# Blue_Pill_v1_0.net
KiCad netlist of a schematic drawn in Altium Designer
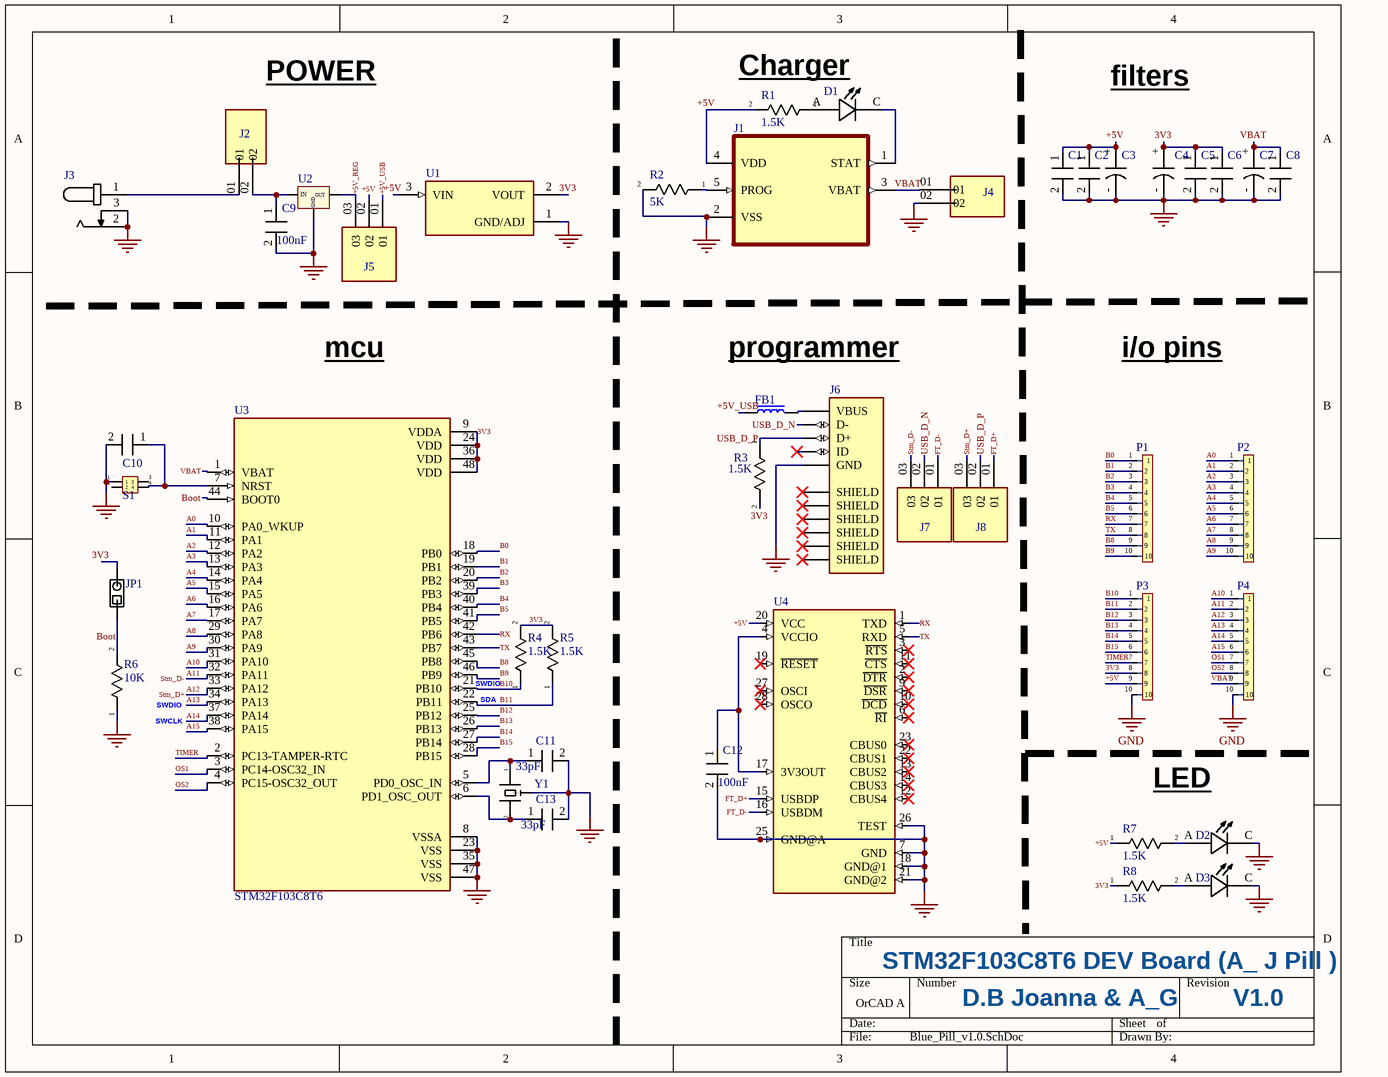
[diagram p0: Blue_Pill_v1.0.SchDoc]

(export (version "E")
  (design (tool "Eeschema 10.0.6"))
  (components
    (comp (ref "C1")
      (value "10nF")
      (footprint "CL21B104KACNNNC")
      (description "0.1 µF ±10% 25V Ceramic Capacitor X7R 0805 (2012 Metric)")
      (libsource (lib "Joanna_Integrated_Library") (part "CL21B104KACNNNC"))
    )
    (comp (ref "C2")
      (value "100nF")
      (footprint "CL21B104KACNNNC")
      (description "0.1 µF ±10% 25V Ceramic Capacitor X7R 0805 (2012 Metric)")
      (libsource (lib "Joanna_Integrated_Library") (part "CL21B104KACNNNC"))
    )
    (comp (ref "C3")
      (value "2.2UF")
      (footprint "10SVP4R7M")
      (description "4.7 µF 10 V Aluminum - Polymer Capacitors Radial, Can - SMD 240mOhm 2000 Hrs @ 105°C")
      (libsource (lib "Joanna_Integrated_Library") (part "10SVP4R7M"))
    )
    (comp (ref "C4")
      (value "2.2UF")
      (footprint "10SVP4R7M")
      (description "4.7 µF 10 V Aluminum - Polymer Capacitors Radial, Can - SMD 240mOhm 2000 Hrs @ 105°C")
      (libsource (lib "Joanna_Integrated_Library") (part "10SVP4R7M"))
    )
    (comp (ref "C5")
      (value "100nF")
      (footprint "CL21B104KACNNNC")
      (description "0.1 µF ±10% 25V Ceramic Capacitor X7R 0805 (2012 Metric)")
      (libsource (lib "Joanna_Integrated_Library") (part "CL21B104KACNNNC"))
    )
    (comp (ref "C6")
      (value "10nF")
      (footprint "CL21B104KACNNNC")
      (description "0.1 µF ±10% 25V Ceramic Capacitor X7R 0805 (2012 Metric)")
      (libsource (lib "Joanna_Integrated_Library") (part "CL21B104KACNNNC"))
    )
    (comp (ref "C7")
      (value "2.2UF")
      (footprint "10SVP4R7M")
      (description "4.7 µF 10 V Aluminum - Polymer Capacitors Radial, Can - SMD 240mOhm 2000 Hrs @ 105°C")
      (libsource (lib "Joanna_Integrated_Library") (part "10SVP4R7M"))
    )
    (comp (ref "C8")
      (value "100nF")
      (footprint "CL21B104KACNNNC")
      (description "0.1 µF ±10% 25V Ceramic Capacitor X7R 0805 (2012 Metric)")
      (libsource (lib "Joanna_Integrated_Library") (part "CL21B104KACNNNC"))
    )
    (comp (ref "C9")
      (value "100nF")
      (footprint "CL21B104KACNNNC")
      (description "0.1 µF ±10% 25V Ceramic Capacitor X7R 0805 (2012 Metric)")
      (libsource (lib "Joanna_Integrated_Library") (part "CL21B104KACNNNC"))
    )
    (comp (ref "C10")
      (value "100nF")
      (footprint "CL21B104KACNNNC")
      (description "0.1 µF ±10% 25V Ceramic Capacitor X7R 0805 (2012 Metric)")
      (libsource (lib "Joanna_Integrated_Library") (part "CL21B104KACNNNC"))
    )
    (comp (ref "C11")
      (value "33pF")
      (footprint "CC0805JKX7R7BB105")
      (description "1 µF ±5% 16V Ceramic Capacitor X7R 0805 (2012 Metric)")
      (libsource (lib "Joanna_Integrated_Library") (part "CC0805JKX7R7BB105"))
    )
    (comp (ref "C12")
      (value "100nF")
      (footprint "CL21B104KACNNNC")
      (description "0.1 µF ±10% 25V Ceramic Capacitor X7R 0805 (2012 Metric)")
      (libsource (lib "Joanna_Integrated_Library") (part "CL21B104KACNNNC"))
    )
    (comp (ref "C13")
      (value "33pF")
      (footprint "CC0805JKX7R7BB105")
      (description "1 µF ±5% 16V Ceramic Capacitor X7R 0805 (2012 Metric)")
      (libsource (lib "Joanna_Integrated_Library") (part "CC0805JKX7R7BB105"))
    )
    (comp (ref "D1")
      (value "LEDC2012X70N")
      (footprint "LEDC2012X70N")
      (description "SMD LED 0805")
      (libsource (lib "Joanna_Integrated_Library") (part "LEDC2012X70N"))
    )
    (comp (ref "D2")
      (value "LEDC2012X70N")
      (footprint "LEDC2012X70N")
      (description "SMD LED 0805")
      (libsource (lib "") (part "LEDC2012X70N_1"))
    )
    (comp (ref "D3")
      (value "LEDC2012X70N")
      (footprint "LEDC2012X70N")
      (description "SMD LED 0805")
      (libsource (lib "") (part "LEDC2012X70N_1"))
    )
    (comp (ref "FB1")
      (value "FB0805")
      (footprint "FB_0805")
      (description "Ferrite Bead SMD 0805")
      (libsource (lib "ph_lib") (part "FB_0805"))
    )
    (comp (ref "J1")
      (value "MCP73831T-2ACI/OT")
      (footprint "MCP73831_SOT95P280X145-5N")
      (description "Charger IC Lithium Ion/Polymer SOT-23-5")
      (fields (field (name "MF") "Microchip"))
      (libsource (lib "Joanna_Integrated_Library") (part "MCP73831T-2ACI/OT"))
    )
    (comp (ref "J2")
      (value "PINHEADER_2_61300211121")
      (footprint "PINHEADER_2_WURTH_61300211121")
      (description "Connector Header Through Hole 2 position 0.100 (2.54mm)")
      (fields (field (name "MF") "Wurth Elektronik") (field (name "MP") "61300211121"))
      (libsource (lib "") (part "PINHEADER_2_61300211121_1"))
    )
    (comp (ref "J3")
      (value "PJ-002AH")
      (footprint "PJ-002AH")
      (description "2.0 x 6.5 mm, 5.0 A, Horizontal, Through Hole, Dc Power Jack Connector")
      (libsource (lib "Joanna_Integrated_Library") (part "PJ-002AH"))
    )
    (comp (ref "J4")
      (value "PINHEADER_2_61300211121")
      (footprint "PINHEADER_2_WURTH_61300211121")
      (description "Connector Header Through Hole 2 position 0.100 (2.54mm)")
      (fields (field (name "MF") "Wurth Elektronik") (field (name "MP") "61300211121"))
      (libsource (lib "Joanna_Integrated_Library") (part "PINHEADER_2_61300211121"))
    )
    (comp (ref "J5")
      (value "PinHead_M_TSW-103-07-G-S")
      (footprint "PinHeader_M_SAMTEC_TSW-103-07-G-S")
      (fields (field (name "MP") "altium_native_batch"))
      (libsource (lib "Joanna_Integrated_Library") (part "PinHead_M_TSW-103-07-G-S"))
    )
    (comp (ref "J6")
      (value "USB_MICRO_USB3076-XX-X_REVC5")
      (footprint "USB_MICRO_GCT_USB3076-XX-X_REVC5")
      (fields (field (name "MP") "USB3076-30-A") (field (name "MF") "Global Connector Technology"))
      (libsource (lib "Joanna_Integrated_Library") (part "USB_MICRO_USB3076-XX-X_REVC5"))
    )
    (comp (ref "J7")
      (value "PinHead_M_TSW-103-07-G-S")
      (footprint "PinHeader_M_SAMTEC_TSW-103-07-G-S")
      (fields (field (name "MP") "altium_native_batch"))
      (libsource (lib "Joanna_Integrated_Library") (part "PinHead_M_TSW-103-07-G-S"))
    )
    (comp (ref "J8")
      (value "PinHead_M_TSW-103-07-G-S")
      (footprint "PinHeader_M_SAMTEC_TSW-103-07-G-S")
      (fields (field (name "MP") "altium_native_batch"))
      (libsource (lib "Joanna_Integrated_Library") (part "PinHead_M_TSW-103-07-G-S"))
    )
    (comp (ref "JP1")
      (value "Solder Jumper")
      (footprint "SolderJumper_Single")
      (description "Solder Jumper Single 0.5mm Pitch")
      (libsource (lib "ph_lib") (part "SolderJumper_Single"))
    )
    (comp (ref "P1")
      (value "NPPN101BFCN-RC")
      (footprint "NPPN101BFCN-RC")
      (description "10 Position Header Connector 0.079\" (2.00mm) Through Hole Gold")
      (libsource (lib "Joanna_Integrated_Library") (part "NPPN101BFCN-RC"))
    )
    (comp (ref "P2")
      (value "NPPN101BFCN-RC")
      (footprint "NPPN101BFCN-RC")
      (description "10 Position Header Connector 0.079\" (2.00mm) Through Hole Gold")
      (libsource (lib "Joanna_Integrated_Library") (part "NPPN101BFCN-RC"))
    )
    (comp (ref "P3")
      (value "NPPN101BFCN-RC")
      (footprint "NPPN101BFCN-RC")
      (description "10 Position Header Connector 0.079\" (2.00mm) Through Hole Gold")
      (libsource (lib "Joanna_Integrated_Library") (part "NPPN101BFCN-RC"))
    )
    (comp (ref "P4")
      (value "NPPN101BFCN-RC")
      (footprint "NPPN101BFCN-RC")
      (description "10 Position Header Connector 0.079\" (2.00mm) Through Hole Gold")
      (libsource (lib "Joanna_Integrated_Library") (part "NPPN101BFCN-RC"))
    )
    (comp (ref "R1")
      (value "1.5K")
      (footprint "RMCF0805FT8K06")
      (description "8.06 kOhms ±1% 0.125W, 1/8W Chip Resistor 0805 (2012 Metric) Automotive AEC-Q200 Thick Film")
      (libsource (lib "Joanna_Integrated_Library") (part "RMCF0805FT8K06"))
    )
    (comp (ref "R2")
      (value "5K")
      (footprint "RMCF0805FT8K06")
      (description "8.06 kOhms ±1% 0.125W, 1/8W Chip Resistor 0805 (2012 Metric) Automotive AEC-Q200 Thick Film")
      (libsource (lib "Joanna_Integrated_Library") (part "RMCF0805FT8K06"))
    )
    (comp (ref "R3")
      (value "1.5K")
      (footprint "RMCF0805FT8K06")
      (description "8.06 kOhms ±1% 0.125W, 1/8W Chip Resistor 0805 (2012 Metric) Automotive AEC-Q200 Thick Film")
      (libsource (lib "Joanna_Integrated_Library") (part "RMCF0805FT8K06"))
    )
    (comp (ref "R4")
      (value "1.5K")
      (footprint "RMCF0805FT8K06")
      (description "8.06 kOhms ±1% 0.125W, 1/8W Chip Resistor 0805 (2012 Metric) Automotive AEC-Q200 Thick Film")
      (libsource (lib "Joanna_Integrated_Library") (part "RMCF0805FT8K06"))
    )
    (comp (ref "R5")
      (value "1.5K")
      (footprint "RMCF0805FT8K06")
      (description "8.06 kOhms ±1% 0.125W, 1/8W Chip Resistor 0805 (2012 Metric) Automotive AEC-Q200 Thick Film")
      (libsource (lib "Joanna_Integrated_Library") (part "RMCF0805FT8K06"))
    )
    (comp (ref "R6")
      (value "10K")
      (footprint "RMCF0805FT8K06")
      (description "8.06 kOhms ±1% 0.125W, 1/8W Chip Resistor 0805 (2012 Metric) Automotive AEC-Q200 Thick Film")
      (libsource (lib "Joanna_Integrated_Library") (part "RMCF0805FT8K06"))
    )
    (comp (ref "R7")
      (value "1.5K")
      (footprint "RMCF0805FT8K06")
      (description "8.06 kOhms ±1% 0.125W, 1/8W Chip Resistor 0805 (2012 Metric) Automotive AEC-Q200 Thick Film")
      (libsource (lib "Joanna_Integrated_Library") (part "RMCF0805FT8K06"))
    )
    (comp (ref "R8")
      (value "1.5K")
      (footprint "RMCF0805FT8K06")
      (description "8.06 kOhms ±1% 0.125W, 1/8W Chip Resistor 0805 (2012 Metric) Automotive AEC-Q200 Thick Film")
      (libsource (lib "Joanna_Integrated_Library") (part "RMCF0805FT8K06"))
    )
    (comp (ref "S1")
      (value "B3SL-1002P")
      (footprint "B3SL-1002P")
      (description "Tactile Switch SPST-NO Top Actuated Surface Mount")
      (libsource (lib "Joanna_Integrated_Library") (part "B3SL-1002P"))
    )
    (comp (ref "U1")
      (value "AMS1117-3.3")
      (footprint "AMS11173v3_SOT229P700X180-4N")
      (description "Sot223/Pkg 1-Amp 3.3-Volt Low Drop Out Voltage Regulatator")
      (fields (field (name "MF") "Advanced Monolithic Systems"))
      (libsource (lib "Joanna_Integrated_Library") (part "AMS1117-3.3"))
    )
    (comp (ref "U2")
      (value "SPX1117M3-L-5-0/TR")
      (footprint "SPX1117M3-L-5-0/TR")
      (description "Linear Voltage Regulator IC Positive Fixed 1 Output 800mA SOT-223-3")
      (libsource (lib "Joanna_Integrated_Library") (part "SPX1117M3-L-5-0/TR"))
    )
    (comp (ref "U3")
      (value "STM32F103C8T6")
      (footprint "STM32F103C8T6")
      (description "ARM® Cortex®-M3 STM32F1 Microcontroller IC 32-Bit 72MHz 64KB (64K x 8) FLASH 48-LQFP (7x7)")
      (fields (field (name "MF") "STMicroelectronics"))
      (libsource (lib "Joanna_Integrated_Library") (part "STM32F103C8T6"))
    )
    (comp (ref "U4")
      (value "INTERFACE-FT232RL(SSOP28)")
      (footprint "fT2332_SSOP28-0.65-10.2X5.2MM")
      (description "USB-Ð¼Ð¾ÑÑ‚, Ð¸Ð½Ñ‚ÐµÑ€Ñ„ÐµÐ¹Ñ USB Ðº UART USB 2.0 UART 28-SSOP")
      (fields (field (name "MP") "FT232RL") (field (name "MF") "FTDI, Future"))
      (libsource (lib "Joanna_Integrated_Library") (part "INTERFACE-FT232RL(SSOP28)"))
    )
    (comp (ref "Y1")
      (value "CSTCE16M0V53-R0")
      (footprint "CSTCE16M0V53-R0")
      (description "16 MHz Ceramic Resonator Built in Capacitor 15 pF ±0.3% -20°C ~ 80°C Surface Mount")
      (libsource (lib "Joanna_Integrated_Library") (part "CSTCE16M0V53-R0"))
    )
  )
  (nets
    (net (code "1") (name "/+5V") (class "Default")
      (node (ref "C1") (pin "1") (pinfunction "1_1") (pintype "passive"))
      (node (ref "C2") (pin "1") (pinfunction "1_1") (pintype "passive"))
      (node (ref "C3") (pin "+") (pinfunction "2_+") (pintype "passive"))
      (node (ref "J1") (pin "4") (pinfunction "VDD_4") (pintype "power_in"))
      (node (ref "J5") (pin "02") (pinfunction "02_02") (pintype "passive"))
      (node (ref "P3") (pin "9") (pinfunction "9_9") (pintype "passive"))
      (node (ref "R1") (pin "2") (pinfunction "2_2") (pintype "passive"))
      (node (ref "R7") (pin "1") (pinfunction "1_1") (pintype "passive"))
      (node (ref "U1") (pin "3") (pinfunction "VIN_3") (pintype "input"))
      (node (ref "U4") (pin "20") (pinfunction "VCC_20") (pintype "input"))
    )
    (net (code "2") (name "/+5V_REG") (class "Default")
      (node (ref "J5") (pin "03") (pinfunction "03_03") (pintype "passive"))
      (node (ref "U2") (pin "3") (pinfunction "OUT_3") (pintype "passive"))
    )
    (net (code "3") (name "/+5V_USB") (class "Default")
      (node (ref "FB1") (pin "1") (pinfunction "1_1") (pintype "passive"))
      (node (ref "J5") (pin "01") (pinfunction "01_01") (pintype "passive"))
    )
    (net (code "4") (name "/3V3") (class "Default")
      (node (ref "C4") (pin "+") (pinfunction "2_+") (pintype "passive"))
      (node (ref "C5") (pin "1") (pinfunction "1_1") (pintype "passive"))
      (node (ref "C6") (pin "1") (pinfunction "1_1") (pintype "passive"))
      (node (ref "JP1") (pin "2") (pinfunction "2_2") (pintype "passive"))
      (node (ref "P3") (pin "8") (pinfunction "8_8") (pintype "passive"))
      (node (ref "R3") (pin "2") (pinfunction "2_2") (pintype "passive"))
      (node (ref "R4") (pin "2") (pinfunction "2_2") (pintype "passive"))
      (node (ref "R5") (pin "2") (pinfunction "2_2") (pintype "passive"))
      (node (ref "R8") (pin "1") (pinfunction "1_1") (pintype "passive"))
      (node (ref "U1") (pin "2") (pinfunction "VOUT_2") (pintype "passive"))
      (node (ref "U3") (pin "24") (pinfunction "VDD_24") (pintype "power_in"))
      (node (ref "U3") (pin "36") (pinfunction "VDD_36") (pintype "power_in"))
      (node (ref "U3") (pin "48") (pinfunction "VDD_48") (pintype "power_in"))
      (node (ref "U3") (pin "9") (pinfunction "VDDA_9") (pintype "power_in"))
    )
    (net (code "5") (name "/A0") (class "Default")
      (node (ref "P2") (pin "1") (pinfunction "1_1") (pintype "passive"))
      (node (ref "U3") (pin "10") (pinfunction "PA0_WKUP_10") (pintype "bidirectional"))
    )
    (net (code "6") (name "/A1") (class "Default")
      (node (ref "P2") (pin "2") (pinfunction "2_2") (pintype "passive"))
      (node (ref "U3") (pin "11") (pinfunction "PA1_11") (pintype "bidirectional"))
    )
    (net (code "7") (name "/A2") (class "Default")
      (node (ref "P2") (pin "3") (pinfunction "3_3") (pintype "passive"))
      (node (ref "U3") (pin "12") (pinfunction "PA2_12") (pintype "bidirectional"))
    )
    (net (code "8") (name "/A3") (class "Default")
      (node (ref "P2") (pin "4") (pinfunction "4_4") (pintype "passive"))
      (node (ref "U3") (pin "13") (pinfunction "PA3_13") (pintype "bidirectional"))
    )
    (net (code "9") (name "/A4") (class "Default")
      (node (ref "P2") (pin "5") (pinfunction "5_5") (pintype "passive"))
      (node (ref "U3") (pin "14") (pinfunction "PA4_14") (pintype "bidirectional"))
    )
    (net (code "10") (name "/A5") (class "Default")
      (node (ref "P2") (pin "6") (pinfunction "6_6") (pintype "passive"))
      (node (ref "U3") (pin "15") (pinfunction "PA5_15") (pintype "bidirectional"))
    )
    (net (code "11") (name "/A6") (class "Default")
      (node (ref "P2") (pin "7") (pinfunction "7_7") (pintype "passive"))
      (node (ref "U3") (pin "16") (pinfunction "PA6_16") (pintype "bidirectional"))
    )
    (net (code "12") (name "/A7") (class "Default")
      (node (ref "P2") (pin "8") (pinfunction "8_8") (pintype "passive"))
      (node (ref "U3") (pin "17") (pinfunction "PA7_17") (pintype "bidirectional"))
    )
    (net (code "13") (name "/A8") (class "Default")
      (node (ref "P2") (pin "9") (pinfunction "9_9") (pintype "passive"))
      (node (ref "U3") (pin "29") (pinfunction "PA8_29") (pintype "bidirectional"))
    )
    (net (code "14") (name "/A9") (class "Default")
      (node (ref "P2") (pin "10") (pinfunction "10_10") (pintype "passive"))
      (node (ref "U3") (pin "30") (pinfunction "PA9_30") (pintype "bidirectional"))
    )
    (net (code "15") (name "/A10") (class "Default")
      (node (ref "P4") (pin "1") (pinfunction "1_1") (pintype "passive"))
      (node (ref "U3") (pin "31") (pinfunction "PA10_31") (pintype "bidirectional"))
    )
    (net (code "16") (name "/A11") (class "Default")
      (node (ref "J7") (pin "03") (pinfunction "03_03") (pintype "passive"))
      (node (ref "P4") (pin "2") (pinfunction "2_2") (pintype "passive"))
      (node (ref "U3") (pin "32") (pinfunction "PA11_32") (pintype "bidirectional"))
    )
    (net (code "17") (name "/A12") (class "Default")
      (node (ref "J8") (pin "03") (pinfunction "03_03") (pintype "passive"))
      (node (ref "P4") (pin "3") (pinfunction "3_3") (pintype "passive"))
      (node (ref "U3") (pin "33") (pinfunction "PA12_33") (pintype "bidirectional"))
    )
    (net (code "18") (name "/A13") (class "Default")
      (node (ref "P4") (pin "4") (pinfunction "4_4") (pintype "passive"))
      (node (ref "U3") (pin "34") (pinfunction "PA13_34") (pintype "bidirectional"))
    )
    (net (code "19") (name "/A14") (class "Default")
      (node (ref "P4") (pin "5") (pinfunction "5_5") (pintype "passive"))
      (node (ref "U3") (pin "37") (pinfunction "PA14_37") (pintype "bidirectional"))
    )
    (net (code "20") (name "/A15") (class "Default")
      (node (ref "P4") (pin "6") (pinfunction "6_6") (pintype "passive"))
      (node (ref "U3") (pin "38") (pinfunction "PA15_38") (pintype "bidirectional"))
    )
    (net (code "21") (name "/B0") (class "Default")
      (node (ref "P1") (pin "1") (pinfunction "1_1") (pintype "passive"))
      (node (ref "U3") (pin "18") (pinfunction "PB0_18") (pintype "bidirectional"))
    )
    (net (code "22") (name "/B1") (class "Default")
      (node (ref "P1") (pin "2") (pinfunction "2_2") (pintype "passive"))
      (node (ref "U3") (pin "19") (pinfunction "PB1_19") (pintype "bidirectional"))
    )
    (net (code "23") (name "/B2") (class "Default")
      (node (ref "P1") (pin "3") (pinfunction "3_3") (pintype "passive"))
      (node (ref "U3") (pin "20") (pinfunction "PB2_20") (pintype "bidirectional"))
    )
    (net (code "24") (name "/B3") (class "Default")
      (node (ref "P1") (pin "4") (pinfunction "4_4") (pintype "passive"))
      (node (ref "U3") (pin "39") (pinfunction "PB3_39") (pintype "bidirectional"))
    )
    (net (code "25") (name "/B4") (class "Default")
      (node (ref "P1") (pin "5") (pinfunction "5_5") (pintype "passive"))
      (node (ref "U3") (pin "40") (pinfunction "PB4_40") (pintype "bidirectional"))
    )
    (net (code "26") (name "/B5") (class "Default")
      (node (ref "P1") (pin "6") (pinfunction "6_6") (pintype "passive"))
      (node (ref "U3") (pin "41") (pinfunction "PB5_41") (pintype "bidirectional"))
    )
    (net (code "27") (name "/B8") (class "Default")
      (node (ref "P1") (pin "9") (pinfunction "9_9") (pintype "passive"))
      (node (ref "U3") (pin "45") (pinfunction "PB8_45") (pintype "bidirectional"))
    )
    (net (code "28") (name "/B9") (class "Default")
      (node (ref "P1") (pin "10") (pinfunction "10_10") (pintype "passive"))
      (node (ref "U3") (pin "46") (pinfunction "PB9_46") (pintype "bidirectional"))
    )
    (net (code "29") (name "/B10") (class "Default")
      (node (ref "P3") (pin "1") (pinfunction "1_1") (pintype "passive"))
      (node (ref "R4") (pin "1") (pinfunction "1_1") (pintype "passive"))
      (node (ref "U3") (pin "21") (pinfunction "PB10_21") (pintype "bidirectional"))
    )
    (net (code "30") (name "/B11") (class "Default")
      (node (ref "P3") (pin "2") (pinfunction "2_2") (pintype "passive"))
      (node (ref "R5") (pin "1") (pinfunction "1_1") (pintype "passive"))
      (node (ref "U3") (pin "22") (pinfunction "PB11_22") (pintype "bidirectional"))
    )
    (net (code "31") (name "/B12") (class "Default")
      (node (ref "P3") (pin "3") (pinfunction "3_3") (pintype "passive"))
      (node (ref "U3") (pin "25") (pinfunction "PB12_25") (pintype "bidirectional"))
    )
    (net (code "32") (name "/B13") (class "Default")
      (node (ref "P3") (pin "4") (pinfunction "4_4") (pintype "passive"))
      (node (ref "U3") (pin "26") (pinfunction "PB13_26") (pintype "bidirectional"))
    )
    (net (code "33") (name "/B14") (class "Default")
      (node (ref "P3") (pin "5") (pinfunction "5_5") (pintype "passive"))
      (node (ref "U3") (pin "27") (pinfunction "PB14_27") (pintype "bidirectional"))
    )
    (net (code "34") (name "/B15") (class "Default")
      (node (ref "P3") (pin "6") (pinfunction "6_6") (pintype "passive"))
      (node (ref "U3") (pin "28") (pinfunction "PB15_28") (pintype "bidirectional"))
    )
    (net (code "35") (name "/Boot") (class "Default")
      (node (ref "JP1") (pin "1") (pinfunction "1_1") (pintype "passive"))
      (node (ref "R6") (pin "2") (pinfunction "2_2") (pintype "passive"))
      (node (ref "U3") (pin "44") (pinfunction "BOOT0_44") (pintype "input"))
    )
    (net (code "36") (name "/FT_D+") (class "Default")
      (node (ref "J8") (pin "01") (pinfunction "01_01") (pintype "passive"))
      (node (ref "U4") (pin "15") (pinfunction "USBDP_15") (pintype "input"))
    )
    (net (code "37") (name "/FT_D-") (class "Default")
      (node (ref "J7") (pin "01") (pinfunction "01_01") (pintype "passive"))
      (node (ref "U4") (pin "16") (pinfunction "USBDM_16") (pintype "input"))
    )
    (net (code "38") (name "/OS1") (class "Default")
      (node (ref "P4") (pin "7") (pinfunction "7_7") (pintype "passive"))
      (node (ref "U3") (pin "3") (pinfunction "PC14-OSC32_IN_3") (pintype "bidirectional"))
    )
    (net (code "39") (name "/OS2") (class "Default")
      (node (ref "P4") (pin "8") (pinfunction "8_8") (pintype "passive"))
      (node (ref "U3") (pin "4") (pinfunction "PC15-OSC32_OUT_4") (pintype "bidirectional"))
    )
    (net (code "40") (name "/RX") (class "Default")
      (node (ref "P1") (pin "7") (pinfunction "7_7") (pintype "passive"))
      (node (ref "U3") (pin "42") (pinfunction "PB6_42") (pintype "bidirectional"))
      (node (ref "U4") (pin "1") (pinfunction "TXD_1") (pintype "input"))
    )
    (net (code "41") (name "/TIMER") (class "Default")
      (node (ref "P3") (pin "7") (pinfunction "7_7") (pintype "passive"))
      (node (ref "U3") (pin "2") (pinfunction "PC13-TAMPER-RTC_2") (pintype "bidirectional"))
    )
    (net (code "42") (name "/TX") (class "Default")
      (node (ref "P1") (pin "8") (pinfunction "8_8") (pintype "passive"))
      (node (ref "U3") (pin "43") (pinfunction "PB7_43") (pintype "bidirectional"))
      (node (ref "U4") (pin "5") (pinfunction "RXD_5") (pintype "input"))
    )
    (net (code "43") (name "/USB_D_N") (class "Default")
      (node (ref "J6") (pin "2") (pinfunction "D-_2") (pintype "bidirectional"))
      (node (ref "J7") (pin "02") (pinfunction "02_02") (pintype "passive"))
    )
    (net (code "44") (name "/USB_D_P") (class "Default")
      (node (ref "J6") (pin "3") (pinfunction "D+_3") (pintype "bidirectional"))
      (node (ref "J8") (pin "02") (pinfunction "02_02") (pintype "passive"))
      (node (ref "R3") (pin "1") (pinfunction "1_1") (pintype "passive"))
    )
    (net (code "45") (name "/VBAT") (class "Default")
      (node (ref "C7") (pin "+") (pinfunction "2_+") (pintype "passive"))
      (node (ref "C8") (pin "1") (pinfunction "1_1") (pintype "passive"))
      (node (ref "J1") (pin "3") (pinfunction "VBAT_3") (pintype "output"))
      (node (ref "J4") (pin "01") (pinfunction "01_01") (pintype "passive"))
      (node (ref "P4") (pin "9") (pinfunction "9_9") (pintype "passive"))
      (node (ref "U3") (pin "1") (pinfunction "VBAT_1") (pintype "bidirectional"))
    )
    (net (code "46") (name "GND") (class "Default")
      (node (ref "C1") (pin "2") (pinfunction "2_2") (pintype "passive"))
      (node (ref "C10") (pin "2") (pinfunction "2_2") (pintype "passive"))
      (node (ref "C11") (pin "2") (pinfunction "2_2") (pintype "passive"))
      (node (ref "C12") (pin "2") (pinfunction "2_2") (pintype "passive"))
      (node (ref "C13") (pin "2") (pinfunction "2_2") (pintype "passive"))
      (node (ref "C2") (pin "2") (pinfunction "2_2") (pintype "passive"))
      (node (ref "C3") (pin "-") (pinfunction "1_-") (pintype "passive"))
      (node (ref "C4") (pin "-") (pinfunction "1_-") (pintype "passive"))
      (node (ref "C5") (pin "2") (pinfunction "2_2") (pintype "passive"))
      (node (ref "C6") (pin "2") (pinfunction "2_2") (pintype "passive"))
      (node (ref "C7") (pin "-") (pinfunction "1_-") (pintype "passive"))
      (node (ref "C8") (pin "2") (pinfunction "2_2") (pintype "passive"))
      (node (ref "C9") (pin "2") (pinfunction "2_2") (pintype "passive"))
      (node (ref "D2") (pin "C") (pinfunction "C_C") (pintype "passive"))
      (node (ref "D3") (pin "C") (pinfunction "C_C") (pintype "passive"))
      (node (ref "J1") (pin "2") (pinfunction "VSS_2") (pintype "power_in"))
      (node (ref "J3") (pin "2") (pinfunction "2_2") (pintype "passive"))
      (node (ref "J3") (pin "3") (pinfunction "3_3") (pintype "passive"))
      (node (ref "J4") (pin "02") (pinfunction "02_02") (pintype "passive"))
      (node (ref "J6") (pin "5") (pinfunction "GND_5") (pintype "power_in"))
      (node (ref "P3") (pin "10") (pinfunction "10_10") (pintype "passive"))
      (node (ref "P4") (pin "10") (pinfunction "10_10") (pintype "passive"))
      (node (ref "R2") (pin "2") (pinfunction "2_2") (pintype "passive"))
      (node (ref "R6") (pin "1") (pinfunction "1_1") (pintype "passive"))
      (node (ref "S1") (pin "1") (pinfunction "1_1") (pintype "passive"))
      (node (ref "U1") (pin "1") (pinfunction "GND/ADJ_1") (pintype "power_in"))
      (node (ref "U2") (pin "2") (pinfunction "GND_2") (pintype "power_in"))
      (node (ref "U3") (pin "23") (pinfunction "VSS_23") (pintype "power_in"))
      (node (ref "U3") (pin "35") (pinfunction "VSS_35") (pintype "power_in"))
      (node (ref "U3") (pin "47") (pinfunction "VSS_47") (pintype "power_in"))
      (node (ref "U3") (pin "8") (pinfunction "VSSA_8") (pintype "power_in"))
      (node (ref "U4") (pin "18") (pinfunction "GND@1_18") (pintype "input"))
      (node (ref "U4") (pin "21") (pinfunction "GND@2_21") (pintype "input"))
      (node (ref "U4") (pin "25") (pinfunction "GND@A_25") (pintype "input"))
      (node (ref "U4") (pin "26") (pinfunction "TEST_26") (pintype "input"))
      (node (ref "U4") (pin "7") (pinfunction "GND_7") (pintype "input"))
      (node (ref "Y1") (pin "Gnd") (pinfunction "Gnd_Gnd") (pintype "passive"))
    )
    (net (code "47") (name "Net-(D1-PadA)") (class "Default")
      (node (ref "D1") (pin "A") (pinfunction "A_A") (pintype "passive"))
      (node (ref "R1") (pin "1") (pinfunction "1_1") (pintype "passive"))
    )
    (net (code "48") (name "Net-(D2-PadA)") (class "Default")
      (node (ref "D2") (pin "A") (pinfunction "A_A") (pintype "passive"))
      (node (ref "R7") (pin "2") (pinfunction "2_2") (pintype "passive"))
    )
    (net (code "49") (name "Net-(D3-PadA)") (class "Default")
      (node (ref "D3") (pin "A") (pinfunction "A_A") (pintype "passive"))
      (node (ref "R8") (pin "2") (pinfunction "2_2") (pintype "passive"))
    )
    (net (code "50") (name "Net-(J1-PROG)") (class "Default")
      (node (ref "J1") (pin "5") (pinfunction "PROG_5") (pintype "input"))
      (node (ref "R2") (pin "1") (pinfunction "1_1") (pintype "passive"))
    )
    (net (code "51") (name "Net-(J1-STAT)") (class "Default")
      (node (ref "D1") (pin "C") (pinfunction "C_C") (pintype "passive"))
      (node (ref "J1") (pin "1") (pinfunction "STAT_1") (pintype "output"))
    )
    (net (code "52") (name "Net-(J2-Pad01)") (class "Default")
      (node (ref "J2") (pin "01") (pinfunction "01_01") (pintype "passive"))
      (node (ref "J3") (pin "1") (pinfunction "1_1") (pintype "passive"))
    )
    (net (code "53") (name "Net-(J6-VBUS)") (class "Default")
      (node (ref "FB1") (pin "2") (pinfunction "2_2") (pintype "passive"))
      (node (ref "J6") (pin "1") (pinfunction "VBUS_1") (pintype "power_in"))
    )
    (net (code "54") (name "Net-(U2-IN)") (class "Default")
      (node (ref "C9") (pin "1") (pinfunction "1_1") (pintype "passive"))
      (node (ref "J2") (pin "02") (pinfunction "02_02") (pintype "passive"))
      (node (ref "U2") (pin "1") (pinfunction "IN_1") (pintype "input"))
    )
    (net (code "55") (name "Net-(U3-NRST)") (class "Default")
      (node (ref "C10") (pin "1") (pinfunction "1_1") (pintype "passive"))
      (node (ref "S1") (pin "4") (pinfunction "4_4") (pintype "passive"))
      (node (ref "U3") (pin "7") (pinfunction "NRST_7") (pintype "input"))
    )
    (net (code "56") (name "Net-(U3-PD0_OSC_IN)") (class "Default")
      (node (ref "C11") (pin "1") (pinfunction "1_1") (pintype "passive"))
      (node (ref "U3") (pin "5") (pinfunction "PD0_OSC_IN_5") (pintype "bidirectional"))
      (node (ref "Y1") (pin "1") (pinfunction "1_1") (pintype "power_in"))
    )
    (net (code "57") (name "Net-(U3-PD1_OSC_OUT)") (class "Default")
      (node (ref "C13") (pin "1") (pinfunction "1_1") (pintype "passive"))
      (node (ref "U3") (pin "6") (pinfunction "PD1_OSC_OUT_6") (pintype "bidirectional"))
      (node (ref "Y1") (pin "2") (pinfunction "2_2") (pintype "passive"))
    )
    (net (code "58") (name "Net-(U4-3V3OUT)") (class "Default")
      (node (ref "C12") (pin "1") (pinfunction "1_1") (pintype "passive"))
      (node (ref "U4") (pin "17") (pinfunction "3V3OUT_17") (pintype "input"))
      (node (ref "U4") (pin "4") (pinfunction "VCCIO_4") (pintype "input"))
    )
    (net (code "59") (name "unconnected-(J6-ID-Pad4)") (class "Default")
      (node (ref "J6") (pin "4") (pinfunction "ID_4") (pintype "bidirectional+no_connect"))
    )
    (net (code "60") (name "unconnected-(J6-SHIELD-Pad6)") (class "Default")
      (node (ref "J6") (pin "6") (pinfunction "SHIELD_6") (pintype "power_in+no_connect"))
    )
    (net (code "61") (name "unconnected-(J6-SHIELD-Pad7)") (class "Default")
      (node (ref "J6") (pin "7") (pinfunction "SHIELD_7") (pintype "power_in+no_connect"))
    )
    (net (code "62") (name "unconnected-(J6-SHIELD-Pad8)") (class "Default")
      (node (ref "J6") (pin "8") (pinfunction "SHIELD_8") (pintype "power_in+no_connect"))
    )
    (net (code "63") (name "unconnected-(J6-SHIELD-Pad9)") (class "Default")
      (node (ref "J6") (pin "9") (pinfunction "SHIELD_9") (pintype "power_in+no_connect"))
    )
    (net (code "64") (name "unconnected-(J6-SHIELD-Pad10)") (class "Default")
      (node (ref "J6") (pin "10") (pinfunction "SHIELD_10") (pintype "power_in+no_connect"))
    )
    (net (code "65") (name "unconnected-(J6-SHIELD-Pad11)") (class "Default")
      (node (ref "J6") (pin "11") (pinfunction "SHIELD_11") (pintype "power_in+no_connect"))
    )
    (net (code "66") (name "unconnected-(S1-Pad2)") (class "Default")
      (node (ref "S1") (pin "2") (pinfunction "2_2") (pintype "passive"))
    )
    (net (code "67") (name "unconnected-(S1-Pad3)") (class "Default")
      (node (ref "S1") (pin "3") (pinfunction "3_3") (pintype "passive"))
    )
    (net (code "68") (name "unconnected-(U4-CBUS0-Pad23)") (class "Default")
      (node (ref "U4") (pin "23") (pinfunction "CBUS0_23") (pintype "input+no_connect"))
    )
    (net (code "69") (name "unconnected-(U4-CBUS1-Pad22)") (class "Default")
      (node (ref "U4") (pin "22") (pinfunction "CBUS1_22") (pintype "input+no_connect"))
    )
    (net (code "70") (name "unconnected-(U4-CBUS2-Pad13)") (class "Default")
      (node (ref "U4") (pin "13") (pinfunction "CBUS2_13") (pintype "input+no_connect"))
    )
    (net (code "71") (name "unconnected-(U4-CBUS3-Pad14)") (class "Default")
      (node (ref "U4") (pin "14") (pinfunction "CBUS3_14") (pintype "input+no_connect"))
    )
    (net (code "72") (name "unconnected-(U4-CBUS4-Pad12)") (class "Default")
      (node (ref "U4") (pin "12") (pinfunction "CBUS4_12") (pintype "input+no_connect"))
    )
    (net (code "73") (name "unconnected-(U4-OSCI-Pad27)") (class "Default")
      (node (ref "U4") (pin "27") (pinfunction "OSCI_27") (pintype "input+no_connect"))
    )
    (net (code "74") (name "unconnected-(U4-OSCO-Pad28)") (class "Default")
      (node (ref "U4") (pin "28") (pinfunction "OSCO_28") (pintype "input+no_connect"))
    )
    (net (code "75") (name "unconnected-(U4-~{CTS}-Pad11)") (class "Default")
      (node (ref "U4") (pin "11") (pinfunction "~{CTS}_11") (pintype "input+no_connect"))
    )
    (net (code "76") (name "unconnected-(U4-~{DCD}-Pad10)") (class "Default")
      (node (ref "U4") (pin "10") (pinfunction "~{DCD}_10") (pintype "input+no_connect"))
    )
    (net (code "77") (name "unconnected-(U4-~{DSR}-Pad9)") (class "Default")
      (node (ref "U4") (pin "9") (pinfunction "~{DSR}_9") (pintype "input+no_connect"))
    )
    (net (code "78") (name "unconnected-(U4-~{DTR}-Pad2)") (class "Default")
      (node (ref "U4") (pin "2") (pinfunction "~{DTR}_2") (pintype "input+no_connect"))
    )
    (net (code "79") (name "unconnected-(U4-~{RESET}-Pad19)") (class "Default")
      (node (ref "U4") (pin "19") (pinfunction "~{RESET}_19") (pintype "input+no_connect"))
    )
    (net (code "80") (name "unconnected-(U4-~{RI}-Pad6)") (class "Default")
      (node (ref "U4") (pin "6") (pinfunction "~{RI}_6") (pintype "input+no_connect"))
    )
    (net (code "81") (name "unconnected-(U4-~{RTS}-Pad3)") (class "Default")
      (node (ref "U4") (pin "3") (pinfunction "~{RTS}_3") (pintype "input+no_connect"))
    )
  )
)
